# Circuit_smart_socet_protopype.net
KiCad netlist of a schematic drawn in Altium Designer
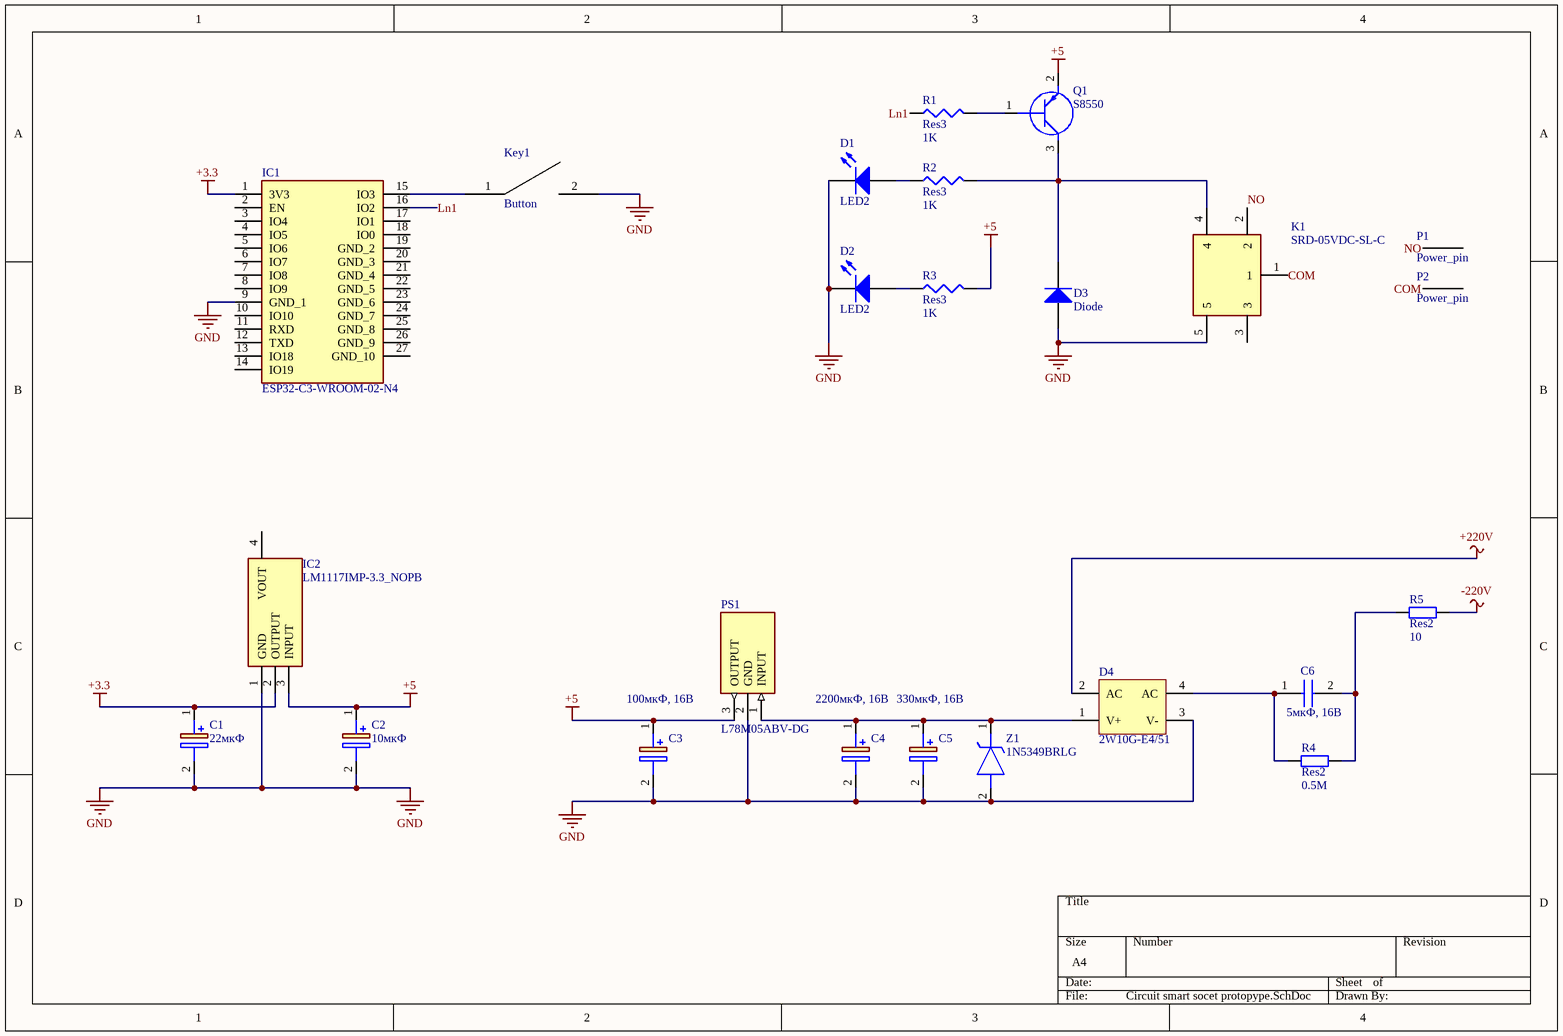
[diagram p0: Circuit smart socet protopype.SchDoc]

(export (version "E")
  (design (tool "Eeschema 10.0.6"))
  (components
    (comp (ref "C1")
      (value "22мкФ")
      (footprint "SamacSys:CAPPRD250W45D655H650")
      (description "Capacitor Polarised")
      (fields
        (field (name "MANUFACTURER_PART_NUMBER") "16MH5100MEFC6.3X5")
        (field (name "MOUSER PART NUMBER") "232-16MH5100MEFC63X5")
      )
      (libsource (lib "SamacSys") (part "16MH5100MEFC6.3X5"))
    )
    (comp (ref "C2")
      (value "10мкФ")
      (footprint "SamacSys:CAPPRD250W45D655H650")
      (description "Capacitor Polarised")
      (fields
        (field (name "MANUFACTURER_PART_NUMBER") "16MH5100MEFC6.3X5")
        (field (name "MOUSER PART NUMBER") "232-16MH5100MEFC63X5")
      )
      (libsource (lib "SamacSys") (part "16MH5100MEFC6.3X5"))
    )
    (comp (ref "C3")
      (value "100мкФ, 16В")
      (footprint "SamacSys:CAPPRD250W45D655H650")
      (description "Capacitor Polarised")
      (fields
        (field (name "MANUFACTURER_PART_NUMBER") "16MH5100MEFC6.3X5")
        (field (name "MOUSER PART NUMBER") "232-16MH5100MEFC63X5")
      )
      (libsource (lib "SamacSys") (part "16MH5100MEFC6.3X5"))
    )
    (comp (ref "C4")
      (value "2200мкФ, 16В")
      (footprint "SamacSys:CAPPRD250W45D655H650")
      (description "Capacitor Polarised")
      (fields
        (field (name "MANUFACTURER_PART_NUMBER") "16MH5100MEFC6.3X5")
        (field (name "MOUSER PART NUMBER") "232-16MH5100MEFC63X5")
      )
      (libsource (lib "SamacSys") (part "16MH5100MEFC6.3X5"))
    )
    (comp (ref "C5")
      (value "330мкФ, 16В")
      (footprint "SamacSys:CAPPRD250W45D655H650")
      (description "Capacitor Polarised")
      (fields
        (field (name "MANUFACTURER_PART_NUMBER") "16MH5100MEFC6.3X5")
        (field (name "MOUSER PART NUMBER") "232-16MH5100MEFC63X5")
      )
      (libsource (lib "SamacSys") (part "16MH5100MEFC6.3X5"))
    )
    (comp (ref "C6")
      (value "5мкФ, 16В")
      (footprint "SamacSys:MKP1G033305F00JSSD")
      (description "Capacitor")
      (fields
        (field (name "MANUFACTURER_PART_NUMBER") "MKP1G033305F00JSSD")
        (field (name "MOUSER PART NUMBER") "505-MKP1G033305F00JS")
      )
      (libsource (lib "SamacSys") (part "MKP1G033305F00JSSD"))
    )
    (comp (ref "D1")
      (value "LED2")
      (footprint "3.2X1.6X1.1")
      (description "Typical RED, GREEN, YELLOW, AMBER GaAs LED")
      (fields (field (name "PUBLISHER") "Altium Limited"))
      (libsource (lib "Miscellaneous Devices") (part "LED2"))
    )
    (comp (ref "D2")
      (value "LED2")
      (footprint "3.2X1.6X1.1")
      (description "Typical RED, GREEN, YELLOW, AMBER GaAs LED")
      (fields (field (name "PUBLISHER") "Altium Limited"))
      (libsource (lib "Miscellaneous Devices") (part "LED2"))
    )
    (comp (ref "D3")
      (value "Diode")
      (footprint "SMC")
      (description "Default Diode")
      (fields (field (name "PUBLISHER") "Altium Limited"))
      (libsource (lib "Miscellaneous Devices") (part "Diode"))
    )
    (comp (ref "D4")
      (value "2W10G-E4/51")
      (footprint "D-46_6A")
      (description "Diode Bridge")
      (fields (field (name "PUBLISHER") "Altium Limited"))
      (libsource (lib "Miscellaneous Devices") (part "Bridge2"))
    )
    (comp (ref "IC1")
      (value "ESP32-C3-WROOM-02-N4")
      (footprint "SamacSys:ESP32C3WROOM02N4")
      (description "Integrated Circuit")
      (fields (field (name "MOUSER PART NUMBER") "356-ESP32C3WROOM02N4"))
      (libsource (lib "SamacSys") (part "ESP32-C3-WROOM-02-N4"))
    )
    (comp (ref "IC2")
      (value "LM1117IMP-3.3_NOPB")
      (footprint "SamacSys:SOT230P700X180-4N")
      (description "Integrated Circuit")
      (fields
        (field (name "MANUFACTURER_PART_NUMBER") "LM1117IMP-3.3/NOPB")
        (field (name "MOUSER PART NUMBER") "926-LM1117IMP3.3NOPB")
      )
      (libsource (lib "*") (part "LM1117IMP-3.3_NOPB"))
    )
    (comp (ref "K1")
      (value "SRD-05VDC-SL-C")
      (footprint "SamacSys:SRD")
      (description "Relay or Contactor")
      (libsource (lib "*") (part "SRD-05VDC-SL-C"))
    )
    (comp (ref "Key1")
      (value "Button")
      (footprint "Button remote")
      (libsource (lib "Schlib1") (part "Button"))
    )
    (comp (ref "P1")
      (value "Power_pin")
      (footprint "Power_hole 7-3")
      (libsource (lib "Schlib1") (part "Power_pin"))
    )
    (comp (ref "P2")
      (value "Power_pin")
      (footprint "Power_hole 7-3")
      (libsource (lib "Schlib1") (part "Power_pin"))
    )
    (comp (ref "PS1")
      (value "L78M05ABV-DG")
      (footprint "SamacSys:TO255P460X1020X2008-3P")
      (description "Power Supply")
      (fields (field (name "MOUSER PART NUMBER") "511-L78M05ABV-DG"))
      (libsource (lib "*") (part "L78M05ABV-DG"))
    )
    (comp (ref "Q1")
      (value "S8550")
      (footprint "SamacSys:SOT95P240X115-3N")
      (description "Transistor BJT PNP")
      (libsource (lib "*") (part "S8550"))
    )
    (comp (ref "R1")
      (value "Res3")
      (footprint "J1-0603")
      (description "Resistor")
      (fields (field (name "ALTIUM_VALUE") "1K") (field (name "PUBLISHER") "Altium Limited"))
      (libsource (lib "Miscellaneous Devices") (part "Res3"))
    )
    (comp (ref "R2")
      (value "Res3")
      (footprint "J1-0603")
      (description "Resistor")
      (fields (field (name "ALTIUM_VALUE") "1K") (field (name "PUBLISHER") "Altium Limited"))
      (libsource (lib "Miscellaneous Devices") (part "Res3"))
    )
    (comp (ref "R3")
      (value "Res3")
      (footprint "J1-0603")
      (description "Resistor")
      (fields (field (name "ALTIUM_VALUE") "1K") (field (name "PUBLISHER") "Altium Limited"))
      (libsource (lib "Miscellaneous Devices") (part "Res3"))
    )
    (comp (ref "R4")
      (value "Res2")
      (footprint "AXIAL-0.4")
      (description "Resistor")
      (fields (field (name "ALTIUM_VALUE") "0.5М") (field (name "PUBLISHER") "Altium Limited"))
      (libsource (lib "Miscellaneous Devices") (part "Res2"))
    )
    (comp (ref "R5")
      (value "Res2")
      (footprint "AXIAL-0.4")
      (description "Resistor")
      (fields (field (name "ALTIUM_VALUE") "10") (field (name "PUBLISHER") "Altium Limited"))
      (libsource (lib "Miscellaneous Devices") (part "Res2"))
    )
    (comp (ref "Z1")
      (value "1N5349BRLG")
      (footprint "SamacSys:DIOAD2260W109L864D349")
      (description "Zener Diode")
      (fields (field (name "MOUSER PART NUMBER") "863-1N5349BRLG"))
      (libsource (lib "*") (part "1N5349BRLG"))
    )
  )
  (nets
    (net (code "1") (name "+3.3") (class "Default")
      (node (ref "C1") (pin "1") (pinfunction "+_1") (pintype "passive"))
      (node (ref "IC1") (pin "1") (pinfunction "3V3_1") (pintype "passive"))
      (node (ref "IC2") (pin "2") (pinfunction "OUTPUT_2") (pintype "passive"))
    )
    (net (code "2") (name "+5") (class "Default")
      (node (ref "C2") (pin "1") (pinfunction "+_1") (pintype "passive"))
      (node (ref "C3") (pin "1") (pinfunction "+_1") (pintype "passive"))
      (node (ref "IC2") (pin "3") (pinfunction "INPUT_3") (pintype "passive"))
      (node (ref "PS1") (pin "3") (pinfunction "OUTPUT_3") (pintype "output"))
      (node (ref "Q1") (pin "2") (pinfunction "E_2") (pintype "passive"))
      (node (ref "R3") (pin "2") (pinfunction "2_2") (pintype "passive"))
    )
    (net (code "3") (name "+220V") (class "Default")
      (node (ref "D4") (pin "2") (pinfunction "AC_2") (pintype "passive"))
    )
    (net (code "4") (name "-220V") (class "Default")
      (node (ref "R5") (pin "2") (pinfunction "2_2") (pintype "passive"))
    )
    (net (code "5") (name "/COM") (class "Default")
      (node (ref "K1") (pin "1") (pinfunction "1_1") (pintype "passive"))
      (node (ref "P2") (pin "1") (pinfunction "0_1") (pintype "passive"))
    )
    (net (code "6") (name "/Ln1") (class "Default")
      (node (ref "IC1") (pin "16") (pinfunction "IO2_16") (pintype "passive"))
      (node (ref "R1") (pin "1") (pinfunction "1_1") (pintype "passive"))
    )
    (net (code "7") (name "/NO") (class "Default")
      (node (ref "K1") (pin "2") (pinfunction "2_2") (pintype "passive"))
      (node (ref "P1") (pin "1") (pinfunction "0_1") (pintype "passive"))
    )
    (net (code "8") (name "GND") (class "Default")
      (node (ref "C1") (pin "2") (pinfunction "-_2") (pintype "passive"))
      (node (ref "C2") (pin "2") (pinfunction "-_2") (pintype "passive"))
      (node (ref "C3") (pin "2") (pinfunction "-_2") (pintype "passive"))
      (node (ref "C4") (pin "2") (pinfunction "-_2") (pintype "passive"))
      (node (ref "C5") (pin "2") (pinfunction "-_2") (pintype "passive"))
      (node (ref "D1") (pin "2") (pinfunction "K_2") (pintype "passive"))
      (node (ref "D2") (pin "2") (pinfunction "K_2") (pintype "passive"))
      (node (ref "D3") (pin "1") (pinfunction "A_1") (pintype "passive"))
      (node (ref "D4") (pin "3") (pinfunction "V-_3") (pintype "passive"))
      (node (ref "IC1") (pin "9") (pinfunction "GND_1_9") (pintype "passive"))
      (node (ref "IC2") (pin "1") (pinfunction "GND_1") (pintype "passive"))
      (node (ref "K1") (pin "5") (pinfunction "5_5") (pintype "passive"))
      (node (ref "Key1") (pin "2") (pinfunction "2_2") (pintype "passive"))
      (node (ref "PS1") (pin "2") (pinfunction "GND_2") (pintype "power_in"))
      (node (ref "Z1") (pin "2") (pinfunction "A_2") (pintype "passive"))
    )
    (net (code "9") (name "Net-(C4-+)") (class "Default")
      (node (ref "C4") (pin "1") (pinfunction "+_1") (pintype "passive"))
      (node (ref "C5") (pin "1") (pinfunction "+_1") (pintype "passive"))
      (node (ref "D4") (pin "1") (pinfunction "V+_1") (pintype "passive"))
      (node (ref "PS1") (pin "1") (pinfunction "INPUT_1") (pintype "input"))
      (node (ref "Z1") (pin "1") (pinfunction "K_1") (pintype "passive"))
    )
    (net (code "10") (name "Net-(C6-Pad1)") (class "Default")
      (node (ref "C6") (pin "1") (pinfunction "1_1") (pintype "passive"))
      (node (ref "D4") (pin "4") (pinfunction "AC_4") (pintype "passive"))
      (node (ref "R4") (pin "1") (pinfunction "1_1") (pintype "passive"))
    )
    (net (code "11") (name "Net-(C6-Pad2)") (class "Default")
      (node (ref "C6") (pin "2") (pinfunction "2_2") (pintype "passive"))
      (node (ref "R4") (pin "2") (pinfunction "2_2") (pintype "passive"))
      (node (ref "R5") (pin "1") (pinfunction "1_1") (pintype "passive"))
    )
    (net (code "12") (name "Net-(D1-A)") (class "Default")
      (node (ref "D1") (pin "1") (pinfunction "A_1") (pintype "passive"))
      (node (ref "R2") (pin "1") (pinfunction "1_1") (pintype "passive"))
    )
    (net (code "13") (name "Net-(D2-A)") (class "Default")
      (node (ref "D2") (pin "1") (pinfunction "A_1") (pintype "passive"))
      (node (ref "R3") (pin "1") (pinfunction "1_1") (pintype "passive"))
    )
    (net (code "14") (name "Net-(D3-K)") (class "Default")
      (node (ref "D3") (pin "2") (pinfunction "K_2") (pintype "passive"))
      (node (ref "K1") (pin "4") (pinfunction "4_4") (pintype "passive"))
      (node (ref "Q1") (pin "3") (pinfunction "C_3") (pintype "passive"))
      (node (ref "R2") (pin "2") (pinfunction "2_2") (pintype "passive"))
    )
    (net (code "15") (name "Net-(IC1-IO3)") (class "Default")
      (node (ref "IC1") (pin "15") (pinfunction "IO3_15") (pintype "passive"))
      (node (ref "Key1") (pin "1") (pinfunction "1_1") (pintype "passive"))
    )
    (net (code "16") (name "Net-(Q1-B)") (class "Default")
      (node (ref "Q1") (pin "1") (pinfunction "B_1") (pintype "passive"))
      (node (ref "R1") (pin "2") (pinfunction "2_2") (pintype "passive"))
    )
    (net (code "17") (name "unconnected-(IC1-EN-Pad2)") (class "Default")
      (node (ref "IC1") (pin "2") (pinfunction "EN_2") (pintype "passive"))
    )
    (net (code "18") (name "unconnected-(IC1-GND_2-Pad19)") (class "Default")
      (node (ref "IC1") (pin "19") (pinfunction "GND_2_19") (pintype "passive"))
    )
    (net (code "19") (name "unconnected-(IC1-GND_3-Pad20)") (class "Default")
      (node (ref "IC1") (pin "20") (pinfunction "GND_3_20") (pintype "passive"))
    )
    (net (code "20") (name "unconnected-(IC1-GND_4-Pad21)") (class "Default")
      (node (ref "IC1") (pin "21") (pinfunction "GND_4_21") (pintype "passive"))
    )
    (net (code "21") (name "unconnected-(IC1-GND_5-Pad22)") (class "Default")
      (node (ref "IC1") (pin "22") (pinfunction "GND_5_22") (pintype "passive"))
    )
    (net (code "22") (name "unconnected-(IC1-GND_6-Pad23)") (class "Default")
      (node (ref "IC1") (pin "23") (pinfunction "GND_6_23") (pintype "passive"))
    )
    (net (code "23") (name "unconnected-(IC1-GND_7-Pad24)") (class "Default")
      (node (ref "IC1") (pin "24") (pinfunction "GND_7_24") (pintype "passive"))
    )
    (net (code "24") (name "unconnected-(IC1-GND_8-Pad25)") (class "Default")
      (node (ref "IC1") (pin "25") (pinfunction "GND_8_25") (pintype "passive"))
    )
    (net (code "25") (name "unconnected-(IC1-GND_9-Pad26)") (class "Default")
      (node (ref "IC1") (pin "26") (pinfunction "GND_9_26") (pintype "passive"))
    )
    (net (code "26") (name "unconnected-(IC1-GND_10-Pad27)") (class "Default")
      (node (ref "IC1") (pin "27") (pinfunction "GND_10_27") (pintype "passive"))
    )
    (net (code "27") (name "unconnected-(IC1-IO0-Pad18)") (class "Default")
      (node (ref "IC1") (pin "18") (pinfunction "IO0_18") (pintype "passive"))
    )
    (net (code "28") (name "unconnected-(IC1-IO1-Pad17)") (class "Default")
      (node (ref "IC1") (pin "17") (pinfunction "IO1_17") (pintype "passive"))
    )
    (net (code "29") (name "unconnected-(IC1-IO4-Pad3)") (class "Default")
      (node (ref "IC1") (pin "3") (pinfunction "IO4_3") (pintype "passive"))
    )
    (net (code "30") (name "unconnected-(IC1-IO5-Pad4)") (class "Default")
      (node (ref "IC1") (pin "4") (pinfunction "IO5_4") (pintype "passive"))
    )
    (net (code "31") (name "unconnected-(IC1-IO6-Pad5)") (class "Default")
      (node (ref "IC1") (pin "5") (pinfunction "IO6_5") (pintype "passive"))
    )
    (net (code "32") (name "unconnected-(IC1-IO7-Pad6)") (class "Default")
      (node (ref "IC1") (pin "6") (pinfunction "IO7_6") (pintype "passive"))
    )
    (net (code "33") (name "unconnected-(IC1-IO8-Pad7)") (class "Default")
      (node (ref "IC1") (pin "7") (pinfunction "IO8_7") (pintype "passive"))
    )
    (net (code "34") (name "unconnected-(IC1-IO9-Pad8)") (class "Default")
      (node (ref "IC1") (pin "8") (pinfunction "IO9_8") (pintype "passive"))
    )
    (net (code "35") (name "unconnected-(IC1-IO10-Pad10)") (class "Default")
      (node (ref "IC1") (pin "10") (pinfunction "IO10_10") (pintype "passive"))
    )
    (net (code "36") (name "unconnected-(IC1-IO18-Pad13)") (class "Default")
      (node (ref "IC1") (pin "13") (pinfunction "IO18_13") (pintype "passive"))
    )
    (net (code "37") (name "unconnected-(IC1-IO19-Pad14)") (class "Default")
      (node (ref "IC1") (pin "14") (pinfunction "IO19_14") (pintype "passive"))
    )
    (net (code "38") (name "unconnected-(IC1-RXD-Pad11)") (class "Default")
      (node (ref "IC1") (pin "11") (pinfunction "RXD_11") (pintype "passive"))
    )
    (net (code "39") (name "unconnected-(IC1-TXD-Pad12)") (class "Default")
      (node (ref "IC1") (pin "12") (pinfunction "TXD_12") (pintype "passive"))
    )
    (net (code "40") (name "unconnected-(IC2-VOUT-Pad4)") (class "Default")
      (node (ref "IC2") (pin "4") (pinfunction "VOUT_4") (pintype "passive"))
    )
    (net (code "41") (name "unconnected-(K1-Pad3)") (class "Default")
      (node (ref "K1") (pin "3") (pinfunction "3_3") (pintype "passive"))
    )
  )
)
